# Bomp-countdown.net
KiCad netlist of a schematic drawn in Altium Designer
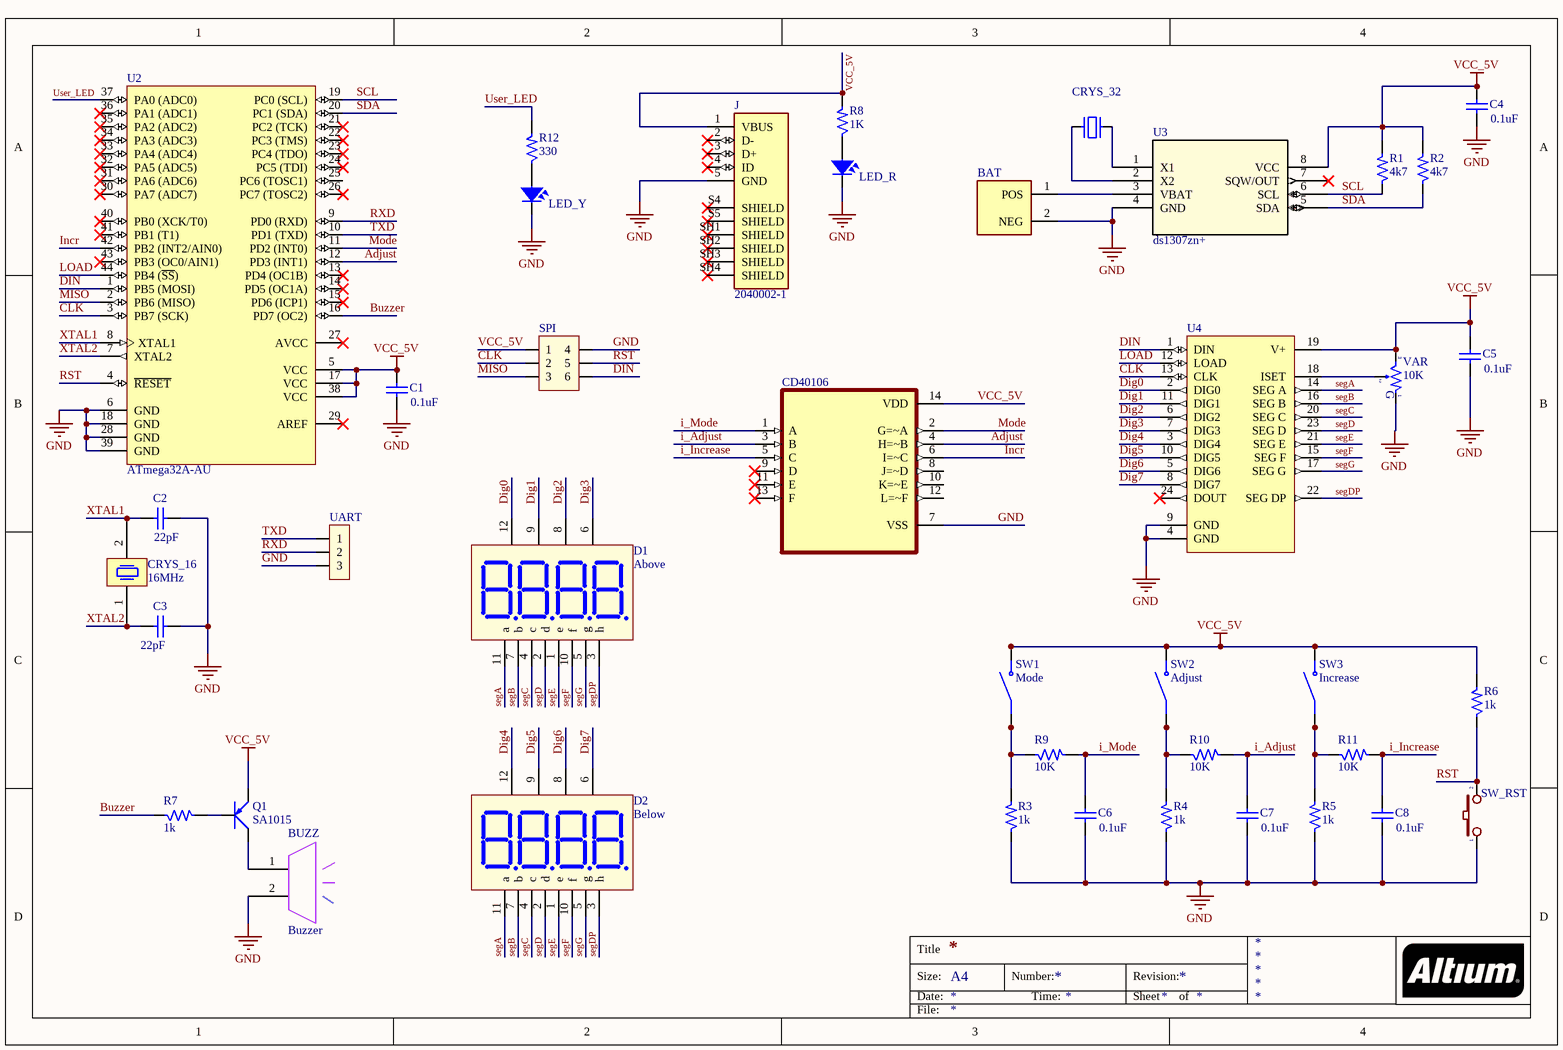
[diagram p0: Bomp-countdown.SchDoc]

(export (version "E")
  (design (tool "Eeschema 10.0.6"))
  (components
    (comp (ref "BAT")
      (value "796136-1")
      (footprint "SnapEDApcb:TE_796136-1")
      (fields (field (name "MF") "TE Connectivity"))
      (libsource (lib "SnapEDAsch") (part "796136-1"))
    )
    (comp (ref "BUZZ")
      (value "Buzzer")
      (footprint "SPEAKER")
      (libsource (lib "My library altium") (part "Buzzer"))
    )
    (comp (ref "C1")
      (value "0.1uF")
      (footprint "C0805")
      (description "Capacitor")
      (fields (field (name "PUBLISHER") "Altium Limited"))
      (libsource (lib "My Library") (part "CapSMD"))
    )
    (comp (ref "C2")
      (value "22pF")
      (footprint "C0805")
      (description "Capacitor")
      (fields (field (name "PUBLISHER") "Altium Limited"))
      (libsource (lib "My Library") (part "CapSMD"))
    )
    (comp (ref "C3")
      (value "22pF")
      (footprint "C0805")
      (description "Capacitor")
      (fields (field (name "PUBLISHER") "Altium Limited"))
      (libsource (lib "My Library") (part "CapSMD"))
    )
    (comp (ref "C4")
      (value "0.1uF")
      (footprint "C0805")
      (description "Capacitor")
      (fields (field (name "PUBLISHER") "Altium Limited"))
      (libsource (lib "My Library") (part "CapSMD"))
    )
    (comp (ref "C5")
      (value "0.1uF")
      (footprint "C0805")
      (description "Capacitor")
      (fields (field (name "PUBLISHER") "Altium Limited"))
      (libsource (lib "My Library") (part "CapSMD"))
    )
    (comp (ref "C6")
      (value "0.1uF")
      (footprint "C0805")
      (description "Capacitor")
      (fields (field (name "PUBLISHER") "Altium Limited"))
      (libsource (lib "My Library") (part "CapSMD"))
    )
    (comp (ref "C7")
      (value "0.1uF")
      (footprint "C0805")
      (description "Capacitor")
      (fields (field (name "PUBLISHER") "Altium Limited"))
      (libsource (lib "My Library") (part "CapSMD"))
    )
    (comp (ref "C8")
      (value "0.1uF")
      (footprint "C0805")
      (description "Capacitor")
      (fields (field (name "PUBLISHER") "Altium Limited"))
      (libsource (lib "My Library") (part "CapSMD"))
    )
    (comp (ref "CD40106")
      (value "CD40106BM")
      (footprint "SOIC127P600X175-14N")
      (description "CMOS Hex Schmitt Triggers 14-SOIC -55 to 125")
      (fields (field (name "MF") "Texas Instruments"))
      (libsource (lib "CD40106BM") (part "CD40106BM"))
    )
    (comp (ref "CRYS_16")
      (value "16MHz")
      (footprint "ABLS2-8.000MHZ-D4Y-T")
      (description "Crystal, 8 MHz, SMD, 11.4mm x 4.7mm, 30 ppm, 18 pF, 30 ppm, ABLS2 Series")
      (fields
        (field (name "MANUFACTURER") "ABRACON")
        (field (name "MANUFACTURER PART NO") "ABLS2-8.000MHZ-D4Y-T")
      )
      (libsource (lib "AltiumOpenLibs") (part "ABLS2-8.000MHZ-D4Y-T"))
    )
    (comp (ref "CRYS_32")
      (value "32.768Khz")
      (footprint "XT32k")
      (description "Crystal, 32.768 KHz, -40 to 85 degC, 3.2 x 1.5 x 0.9 mm SMD")
      (libsource (lib "LIBRARY") (part "XT2"))
    )
    (comp (ref "D1")
      (value "Above")
      (footprint "7SEGQ")
      (description "Four 7 Seg Dipslay")
      (libsource (lib "syhaunguyen") (part "LED7Q"))
    )
    (comp (ref "D2")
      (value "Below")
      (footprint "7SEGQ")
      (description "Four 7 Seg Dipslay")
      (libsource (lib "syhaunguyen") (part "LED7Q"))
    )
    (comp (ref "J")
      (value "2040002-1")
      (footprint "TE_2040002-1")
      (description "Conn Micro USB 2.0 Type B RCP 5 POS 0.65mm Solder RA SMD 5 Terminal 1 Port T/R")
      (fields (field (name "MF") "TE Connectivity"))
      (libsource (lib "u_USB") (part "2040002-1"))
    )
    (comp (ref "LED_R")
      (value "LED SMD")
      (footprint "SM-LED-0805-Red")
      (libsource (lib "syhaunguyen") (part "LED-SMD-0805"))
    )
    (comp (ref "LED_Y")
      (value "LED SMD")
      (footprint "SM-LED-0805-Red")
      (libsource (lib "syhaunguyen") (part "LED-SMD-0805"))
    )
    (comp (ref "Q1")
      (value "SA1015")
      (footprint "SOT23-321")
      (description "PNP 600mW, ECB")
      (libsource (lib "LIBRARY") (part "2SA1015"))
    )
    (comp (ref "R1")
      (value "4k7")
      (footprint "SM-RES-1206")
      (description "Resistor 1/4W")
      (libsource (lib "syhaunguyen") (part "R"))
    )
    (comp (ref "R2")
      (value "4k7")
      (footprint "SM-RES-1206")
      (description "Resistor 1/4W")
      (libsource (lib "syhaunguyen") (part "R"))
    )
    (comp (ref "R3")
      (value "1k")
      (footprint "SM-RES-1206")
      (description "Resistor 1/4W")
      (libsource (lib "syhaunguyen") (part "R"))
    )
    (comp (ref "R4")
      (value "1k")
      (footprint "SM-RES-1206")
      (description "Resistor 1/4W")
      (libsource (lib "syhaunguyen") (part "R"))
    )
    (comp (ref "R5")
      (value "1k")
      (footprint "SM-RES-1206")
      (description "Resistor 1/4W")
      (libsource (lib "syhaunguyen") (part "R"))
    )
    (comp (ref "R6")
      (value "1k")
      (footprint "SM-RES-1206")
      (description "Resistor 1/4W")
      (libsource (lib "syhaunguyen") (part "R"))
    )
    (comp (ref "R7")
      (value "1k")
      (footprint "SM-RES-1206")
      (description "Resistor for buzzer")
      (libsource (lib "syhaunguyen") (part "R"))
    )
    (comp (ref "R8")
      (value "1K")
      (footprint "SM-RES-1206")
      (description "Resistor for buzzer")
      (libsource (lib "syhaunguyen") (part "R"))
    )
    (comp (ref "R9")
      (value "10K")
      (footprint "SM-RES-1206")
      (description "Resistor 1/4W")
      (libsource (lib "syhaunguyen") (part "R"))
    )
    (comp (ref "R10")
      (value "10K")
      (footprint "SM-RES-1206")
      (description "Resistor 1/4W")
      (libsource (lib "syhaunguyen") (part "R"))
    )
    (comp (ref "R11")
      (value "10K")
      (footprint "SM-RES-1206")
      (description "Resistor 1/4W")
      (libsource (lib "syhaunguyen") (part "R"))
    )
    (comp (ref "R12")
      (value "330")
      (footprint "SM-RES-1206")
      (description "Resistor for buzzer")
      (libsource (lib "syhaunguyen") (part "R"))
    )
    (comp (ref "SPI")
      (value "Connector 3x2")
      (footprint "JP3x2")
      (libsource (lib "syhaunguyen") (part "JP3x2"))
    )
    (comp (ref "SW1")
      (value "Mode")
      (footprint "SnapEDApcb:SW_1571527-1")
      (description "Switch Tactile OFF _ON_ Round Button Gull Wing 0.05A 12VDC 0.98N SMD Bulk")
      (fields (field (name "MP") "1571527-1") (field (name "MF") "TE Connectivity"))
      (libsource (lib "SnapEDAsch") (part "1571527-1"))
    )
    (comp (ref "SW2")
      (value "Adjust")
      (footprint "SnapEDApcb:SW_1571527-1")
      (description "Switch Tactile OFF _ON_ Round Button Gull Wing 0.05A 12VDC 0.98N SMD Bulk")
      (fields (field (name "MP") "1571527-1") (field (name "MF") "TE Connectivity"))
      (libsource (lib "SnapEDAsch") (part "1571527-1"))
    )
    (comp (ref "SW3")
      (value "Increase")
      (footprint "SnapEDApcb:SW_1571527-1")
      (description "Switch Tactile OFF _ON_ Round Button Gull Wing 0.05A 12VDC 0.98N SMD Bulk")
      (fields (field (name "MP") "1571527-1") (field (name "MF") "TE Connectivity"))
      (libsource (lib "SnapEDAsch") (part "1571527-1"))
    )
    (comp (ref "SW_RST")
      (value "RST")
      (footprint "SW1-SMD")
      (description "Switch button 2 pin")
      (libsource (lib "LIBRARY") (part "SW2"))
    )
    (comp (ref "U2")
      (value "ATmega32A-AU")
      (footprint "TQFP44")
      (fields (field (name "PUBLISHER") "Altium Limited"))
      (libsource (lib "LIBRARY") (part "ATmega32A-AU"))
    )
    (comp (ref "U3")
      (value "ds1307zn+")
      (footprint "21-0041B_8_MXM")
      (description "No Description Available")
      (fields (field (name "COPYRIGHT") "Copyright (C) 2021 Ultra Librarian. All rights reserved."))
      (libsource (lib "ds1307zn&plus_") (part "ds1307zn+"))
    )
    (comp (ref "U4")
      (value "MAX7219ENG")
      (footprint "SO24")
      (description "Serially Interfaced, 8-Digit LED Display Driver")
      (fields (field (name "PUBLISHER") "Altium Limited"))
      (libsource (lib "LIBRARY") (part "MAX7219ENG"))
    )
    (comp (ref "UART") (value "Jumper 3") (footprint "JP3") (libsource (lib "syhaunguyen") (part "JP3")))
    (comp (ref "VAR")
      (value "10K")
      (footprint "Library:VR-S1")
      (description "Var Resistor")
      (libsource (lib "Library") (part "VR-S"))
    )
  )
  (nets
    (net (code "1") (name "/Adjust") (class "Default")
      (node (ref "CD40106") (pin "4") (pinfunction "H=~B_4") (pintype "output"))
      (node (ref "U2") (pin "12") (pinfunction "PD3_(INT1)_12") (pintype "bidirectional"))
    )
    (net (code "2") (name "/Buzzer") (class "Default")
      (node (ref "R7") (pin "1") (pinfunction "1_1") (pintype "passive"))
      (node (ref "U2") (pin "16") (pinfunction "PD7_(OC2)_16") (pintype "bidirectional"))
    )
    (net (code "3") (name "/CLK") (class "Default")
      (node (ref "SPI") (pin "2") (pinfunction "2_2") (pintype "passive"))
      (node (ref "U2") (pin "3") (pinfunction "PB7_(SCK)_3") (pintype "bidirectional"))
      (node (ref "U4") (pin "13") (pinfunction "CLK_13") (pintype "bidirectional"))
    )
    (net (code "4") (name "/DIN") (class "Default")
      (node (ref "SPI") (pin "6") (pinfunction "6_6") (pintype "passive"))
      (node (ref "U2") (pin "1") (pinfunction "PB5_(MOSI)_1") (pintype "bidirectional"))
      (node (ref "U4") (pin "1") (pinfunction "DIN_1") (pintype "bidirectional"))
    )
    (net (code "5") (name "/Dig0") (class "Default")
      (node (ref "D1") (pin "12") (pinfunction "V1_12") (pintype "passive"))
      (node (ref "U4") (pin "2") (pinfunction "DIG0_2") (pintype "output"))
    )
    (net (code "6") (name "/Dig1") (class "Default")
      (node (ref "D1") (pin "9") (pinfunction "V2_9") (pintype "passive"))
      (node (ref "U4") (pin "11") (pinfunction "DIG1_11") (pintype "output"))
    )
    (net (code "7") (name "/Dig2") (class "Default")
      (node (ref "D1") (pin "8") (pinfunction "V3_8") (pintype "passive"))
      (node (ref "U4") (pin "6") (pinfunction "DIG2_6") (pintype "output"))
    )
    (net (code "8") (name "/Dig3") (class "Default")
      (node (ref "D1") (pin "6") (pinfunction "V4_6") (pintype "passive"))
      (node (ref "U4") (pin "7") (pinfunction "DIG3_7") (pintype "output"))
    )
    (net (code "9") (name "/Dig4") (class "Default")
      (node (ref "D2") (pin "12") (pinfunction "V1_12") (pintype "passive"))
      (node (ref "U4") (pin "3") (pinfunction "DIG4_3") (pintype "output"))
    )
    (net (code "10") (name "/Dig5") (class "Default")
      (node (ref "D2") (pin "9") (pinfunction "V2_9") (pintype "passive"))
      (node (ref "U4") (pin "10") (pinfunction "DIG5_10") (pintype "output"))
    )
    (net (code "11") (name "/Dig6") (class "Default")
      (node (ref "D2") (pin "8") (pinfunction "V3_8") (pintype "passive"))
      (node (ref "U4") (pin "5") (pinfunction "DIG6_5") (pintype "output"))
    )
    (net (code "12") (name "/Dig7") (class "Default")
      (node (ref "D2") (pin "6") (pinfunction "V4_6") (pintype "passive"))
      (node (ref "U4") (pin "8") (pinfunction "DIG7_8") (pintype "output"))
    )
    (net (code "13") (name "/Incr") (class "Default")
      (node (ref "CD40106") (pin "6") (pinfunction "I=~C_6") (pintype "output"))
      (node (ref "U2") (pin "42") (pinfunction "PB2_(INT2/AIN0)_42") (pintype "bidirectional"))
    )
    (net (code "14") (name "/LOAD") (class "Default")
      (node (ref "U2") (pin "44") (pinfunction "PB4_(~{SS})_44") (pintype "bidirectional"))
      (node (ref "U4") (pin "12") (pinfunction "LOAD_12") (pintype "bidirectional"))
    )
    (net (code "15") (name "/MISO") (class "Default")
      (node (ref "SPI") (pin "3") (pinfunction "3_3") (pintype "passive"))
      (node (ref "U2") (pin "2") (pinfunction "PB6_(MISO)_2") (pintype "bidirectional"))
    )
    (net (code "16") (name "/Mode") (class "Default")
      (node (ref "CD40106") (pin "2") (pinfunction "G=~A_2") (pintype "output"))
      (node (ref "U2") (pin "11") (pinfunction "PD2_(INT0)_11") (pintype "bidirectional"))
    )
    (net (code "17") (name "/RST") (class "Default")
      (node (ref "R6") (pin "1") (pinfunction "1_1") (pintype "passive"))
      (node (ref "SPI") (pin "5") (pinfunction "5_5") (pintype "passive"))
      (node (ref "SW_RST") (pin "2") (pinfunction "2_2") (pintype "passive"))
      (node (ref "U2") (pin "4") (pinfunction "~{RESET}_4") (pintype "bidirectional"))
    )
    (net (code "18") (name "/RXD") (class "Default")
      (node (ref "U2") (pin "9") (pinfunction "PD0_(RXD)_9") (pintype "bidirectional"))
      (node (ref "UART") (pin "2") (pinfunction "2_2") (pintype "passive"))
    )
    (net (code "19") (name "/SCL") (class "Default")
      (node (ref "R1") (pin "1") (pinfunction "1_1") (pintype "passive"))
      (node (ref "U2") (pin "19") (pinfunction "PC0_(SCL)_19") (pintype "bidirectional"))
      (node (ref "U3") (pin "6") (pinfunction "SCL_6") (pintype "bidirectional"))
    )
    (net (code "20") (name "/SDA") (class "Default")
      (node (ref "R2") (pin "1") (pinfunction "1_1") (pintype "passive"))
      (node (ref "U2") (pin "20") (pinfunction "PC1_(SDA)_20") (pintype "bidirectional"))
      (node (ref "U3") (pin "5") (pinfunction "SDA_5") (pintype "bidirectional"))
    )
    (net (code "21") (name "/TXD") (class "Default")
      (node (ref "U2") (pin "10") (pinfunction "PD1_(TXD)_10") (pintype "bidirectional"))
      (node (ref "UART") (pin "1") (pinfunction "1_1") (pintype "passive"))
    )
    (net (code "22") (name "/User_LED") (class "Default")
      (node (ref "R12") (pin "2") (pinfunction "2_2") (pintype "passive"))
      (node (ref "U2") (pin "37") (pinfunction "PA0_(ADC0)_37") (pintype "bidirectional"))
    )
    (net (code "23") (name "/XTAL1") (class "Default")
      (node (ref "C2") (pin "1") (pinfunction "1_1") (pintype "passive"))
      (node (ref "CRYS_16") (pin "2") (pinfunction "2_2") (pintype "passive"))
      (node (ref "U2") (pin "8") (pinfunction "XTAL1_8") (pintype "input"))
    )
    (net (code "24") (name "/XTAL2") (class "Default")
      (node (ref "C3") (pin "1") (pinfunction "1_1") (pintype "passive"))
      (node (ref "CRYS_16") (pin "1") (pinfunction "1_1") (pintype "passive"))
      (node (ref "U2") (pin "7") (pinfunction "XTAL2_7") (pintype "output"))
    )
    (net (code "25") (name "/i_Adjust") (class "Default")
      (node (ref "C7") (pin "2") (pinfunction "2_2") (pintype "passive"))
      (node (ref "CD40106") (pin "3") (pinfunction "B_3") (pintype "input"))
      (node (ref "R10") (pin "2") (pinfunction "2_2") (pintype "passive"))
    )
    (net (code "26") (name "/i_Increase") (class "Default")
      (node (ref "C8") (pin "2") (pinfunction "2_2") (pintype "passive"))
      (node (ref "CD40106") (pin "5") (pinfunction "C_5") (pintype "input"))
      (node (ref "R11") (pin "2") (pinfunction "2_2") (pintype "passive"))
    )
    (net (code "27") (name "/i_Mode") (class "Default")
      (node (ref "C6") (pin "2") (pinfunction "2_2") (pintype "passive"))
      (node (ref "CD40106") (pin "1") (pinfunction "A_1") (pintype "input"))
      (node (ref "R9") (pin "2") (pinfunction "2_2") (pintype "passive"))
    )
    (net (code "28") (name "/segA") (class "Default")
      (node (ref "D1") (pin "11") (pinfunction "a_11") (pintype "passive"))
      (node (ref "D2") (pin "11") (pinfunction "a_11") (pintype "passive"))
      (node (ref "U4") (pin "14") (pinfunction "SEG_A_14") (pintype "output"))
    )
    (net (code "29") (name "/segB") (class "Default")
      (node (ref "D1") (pin "7") (pinfunction "b_7") (pintype "passive"))
      (node (ref "D2") (pin "7") (pinfunction "b_7") (pintype "passive"))
      (node (ref "U4") (pin "16") (pinfunction "SEG_B_16") (pintype "output"))
    )
    (net (code "30") (name "/segC") (class "Default")
      (node (ref "D1") (pin "4") (pinfunction "c_4") (pintype "passive"))
      (node (ref "D2") (pin "4") (pinfunction "c_4") (pintype "passive"))
      (node (ref "U4") (pin "20") (pinfunction "SEG_C_20") (pintype "output"))
    )
    (net (code "31") (name "/segD") (class "Default")
      (node (ref "D1") (pin "2") (pinfunction "d_2") (pintype "passive"))
      (node (ref "D2") (pin "2") (pinfunction "d_2") (pintype "passive"))
      (node (ref "U4") (pin "23") (pinfunction "SEG_D_23") (pintype "output"))
    )
    (net (code "32") (name "/segDP") (class "Default")
      (node (ref "D1") (pin "3") (pinfunction "h_3") (pintype "passive"))
      (node (ref "D2") (pin "3") (pinfunction "h_3") (pintype "passive"))
      (node (ref "U4") (pin "22") (pinfunction "SEG_DP_22") (pintype "output"))
    )
    (net (code "33") (name "/segE") (class "Default")
      (node (ref "D1") (pin "1") (pinfunction "e_1") (pintype "passive"))
      (node (ref "D2") (pin "1") (pinfunction "e_1") (pintype "passive"))
      (node (ref "U4") (pin "21") (pinfunction "SEG_E_21") (pintype "output"))
    )
    (net (code "34") (name "/segF") (class "Default")
      (node (ref "D1") (pin "10") (pinfunction "f_10") (pintype "passive"))
      (node (ref "D2") (pin "10") (pinfunction "f_10") (pintype "passive"))
      (node (ref "U4") (pin "15") (pinfunction "SEG_F_15") (pintype "output"))
    )
    (net (code "35") (name "/segG") (class "Default")
      (node (ref "D1") (pin "5") (pinfunction "g_5") (pintype "passive"))
      (node (ref "D2") (pin "5") (pinfunction "g_5") (pintype "passive"))
      (node (ref "U4") (pin "17") (pinfunction "SEG_G_17") (pintype "output"))
    )
    (net (code "36") (name "GND") (class "Default")
      (node (ref "BAT") (pin "2") (pinfunction "NEG_2") (pintype "passive"))
      (node (ref "BUZZ") (pin "2") (pinfunction "2_2") (pintype "passive"))
      (node (ref "C1") (pin "1") (pinfunction "1_1") (pintype "passive"))
      (node (ref "C2") (pin "2") (pinfunction "2_2") (pintype "passive"))
      (node (ref "C3") (pin "2") (pinfunction "2_2") (pintype "passive"))
      (node (ref "C4") (pin "1") (pinfunction "1_1") (pintype "passive"))
      (node (ref "C5") (pin "1") (pinfunction "1_1") (pintype "passive"))
      (node (ref "C6") (pin "1") (pinfunction "1_1") (pintype "passive"))
      (node (ref "C7") (pin "1") (pinfunction "1_1") (pintype "passive"))
      (node (ref "C8") (pin "1") (pinfunction "1_1") (pintype "passive"))
      (node (ref "CD40106") (pin "7") (pinfunction "VSS_7") (pintype "power_in"))
      (node (ref "J") (pin "5") (pinfunction "GND_5") (pintype "power_in"))
      (node (ref "LED_R") (pin "2") (pinfunction "2_2") (pintype "passive"))
      (node (ref "LED_Y") (pin "2") (pinfunction "2_2") (pintype "passive"))
      (node (ref "R3") (pin "1") (pinfunction "1_1") (pintype "passive"))
      (node (ref "R4") (pin "1") (pinfunction "1_1") (pintype "passive"))
      (node (ref "R5") (pin "1") (pinfunction "1_1") (pintype "passive"))
      (node (ref "SPI") (pin "4") (pinfunction "4_4") (pintype "passive"))
      (node (ref "SW_RST") (pin "1") (pinfunction "1_1") (pintype "passive"))
      (node (ref "U2") (pin "18") (pinfunction "GND_18") (pintype "passive"))
      (node (ref "U2") (pin "28") (pinfunction "GND_28") (pintype "passive"))
      (node (ref "U2") (pin "39") (pinfunction "GND_39") (pintype "passive"))
      (node (ref "U2") (pin "6") (pinfunction "GND_6") (pintype "passive"))
      (node (ref "U3") (pin "4") (pinfunction "GND_4") (pintype "power_in"))
      (node (ref "U4") (pin "4") (pinfunction "GND_4") (pintype "power_in"))
      (node (ref "U4") (pin "9") (pinfunction "GND_9") (pintype "power_in"))
      (node (ref "UART") (pin "3") (pinfunction "3_3") (pintype "passive"))
      (node (ref "VAR") (pin "1") (pinfunction "1_1") (pintype "passive"))
    )
    (net (code "37") (name "Net-(BAT-POS)") (class "Default")
      (node (ref "BAT") (pin "1") (pinfunction "POS_1") (pintype "passive"))
      (node (ref "U3") (pin "3") (pinfunction "VBAT_3") (pintype "power_in"))
    )
    (net (code "38") (name "Net-(LED_R-Pad1)") (class "Default")
      (node (ref "LED_R") (pin "1") (pinfunction "1_1") (pintype "passive"))
      (node (ref "R8") (pin "1") (pinfunction "1_1") (pintype "passive"))
    )
    (net (code "39") (name "Net-(LED_Y-Pad1)") (class "Default")
      (node (ref "LED_Y") (pin "1") (pinfunction "1_1") (pintype "passive"))
      (node (ref "R12") (pin "1") (pinfunction "1_1") (pintype "passive"))
    )
    (net (code "40") (name "Net-(Q1-B)") (class "Default")
      (node (ref "Q1") (pin "3") (pinfunction "B_3") (pintype "passive"))
      (node (ref "R7") (pin "2") (pinfunction "2_2") (pintype "passive"))
    )
    (net (code "41") (name "Net-(Q1-C)") (class "Default")
      (node (ref "BUZZ") (pin "1") (pinfunction "1_1") (pintype "passive"))
      (node (ref "Q1") (pin "2") (pinfunction "C_2") (pintype "passive"))
    )
    (net (code "42") (name "Net-(R3-Pad2)") (class "Default")
      (node (ref "R3") (pin "2") (pinfunction "2_2") (pintype "passive"))
      (node (ref "R9") (pin "1") (pinfunction "1_1") (pintype "passive"))
      (node (ref "SW1") (pin "1") (pinfunction "COM_1") (pintype "passive"))
      (node (ref "SW1") (pin "2") (pinfunction "COM_2") (pintype "passive"))
    )
    (net (code "43") (name "Net-(R10-Pad1)") (class "Default")
      (node (ref "R10") (pin "1") (pinfunction "1_1") (pintype "passive"))
      (node (ref "R4") (pin "2") (pinfunction "2_2") (pintype "passive"))
      (node (ref "SW2") (pin "1") (pinfunction "COM_1") (pintype "passive"))
      (node (ref "SW2") (pin "2") (pinfunction "COM_2") (pintype "passive"))
    )
    (net (code "44") (name "Net-(R11-Pad1)") (class "Default")
      (node (ref "R11") (pin "1") (pinfunction "1_1") (pintype "passive"))
      (node (ref "R5") (pin "2") (pinfunction "2_2") (pintype "passive"))
      (node (ref "SW3") (pin "1") (pinfunction "COM_1") (pintype "passive"))
      (node (ref "SW3") (pin "2") (pinfunction "COM_2") (pintype "passive"))
    )
    (net (code "45") (name "Net-(U3-X1)") (class "Default")
      (node (ref "CRYS_32") (pin "2") (pinfunction "2_2") (pintype "passive"))
      (node (ref "U3") (pin "1") (pinfunction "X1_1") (pintype "passive"))
    )
    (net (code "46") (name "Net-(U3-X2)") (class "Default")
      (node (ref "CRYS_32") (pin "1") (pinfunction "1_1") (pintype "passive"))
      (node (ref "U3") (pin "2") (pinfunction "X2_2") (pintype "passive"))
    )
    (net (code "47") (name "Net-(U4-ISET)") (class "Default")
      (node (ref "U4") (pin "18") (pinfunction "ISET_18") (pintype "passive"))
      (node (ref "VAR") (pin "2") (pinfunction "2_2") (pintype "passive"))
    )
    (net (code "48") (name "VCC_5V") (class "Default")
      (node (ref "C1") (pin "2") (pinfunction "2_2") (pintype "passive"))
      (node (ref "C4") (pin "2") (pinfunction "2_2") (pintype "passive"))
      (node (ref "C5") (pin "2") (pinfunction "2_2") (pintype "passive"))
      (node (ref "CD40106") (pin "14") (pinfunction "VDD_14") (pintype "power_in"))
      (node (ref "J") (pin "1") (pinfunction "VBUS_1") (pintype "power_in"))
      (node (ref "Q1") (pin "1") (pinfunction "E_1") (pintype "passive"))
      (node (ref "R1") (pin "2") (pinfunction "2_2") (pintype "passive"))
      (node (ref "R2") (pin "2") (pinfunction "2_2") (pintype "passive"))
      (node (ref "R6") (pin "2") (pinfunction "2_2") (pintype "passive"))
      (node (ref "R8") (pin "2") (pinfunction "2_2") (pintype "passive"))
      (node (ref "SPI") (pin "1") (pinfunction "1_1") (pintype "passive"))
      (node (ref "SW1") (pin "3") (pinfunction "NO_3") (pintype "passive"))
      (node (ref "SW1") (pin "4") (pinfunction "NO_4") (pintype "passive"))
      (node (ref "SW2") (pin "3") (pinfunction "NO_3") (pintype "passive"))
      (node (ref "SW2") (pin "4") (pinfunction "NO_4") (pintype "passive"))
      (node (ref "SW3") (pin "3") (pinfunction "NO_3") (pintype "passive"))
      (node (ref "SW3") (pin "4") (pinfunction "NO_4") (pintype "passive"))
      (node (ref "U2") (pin "17") (pinfunction "VCC_17") (pintype "passive"))
      (node (ref "U2") (pin "38") (pinfunction "VCC_38") (pintype "passive"))
      (node (ref "U2") (pin "5") (pinfunction "VCC_5") (pintype "passive"))
      (node (ref "U3") (pin "8") (pinfunction "VCC_8") (pintype "power_in"))
      (node (ref "U4") (pin "19") (pinfunction "V+_19") (pintype "power_in"))
      (node (ref "VAR") (pin "3") (pinfunction "3_3") (pintype "passive"))
    )
    (net (code "49") (name "unconnected-(CD40106-D-Pad9)") (class "Default")
      (node (ref "CD40106") (pin "9") (pinfunction "D_9") (pintype "input+no_connect"))
    )
    (net (code "50") (name "unconnected-(CD40106-E-Pad11)") (class "Default")
      (node (ref "CD40106") (pin "11") (pinfunction "E_11") (pintype "input+no_connect"))
    )
    (net (code "51") (name "unconnected-(CD40106-F-Pad13)") (class "Default")
      (node (ref "CD40106") (pin "13") (pinfunction "F_13") (pintype "input+no_connect"))
    )
    (net (code "52") (name "unconnected-(CD40106-J=~D-Pad8)") (class "Default")
      (node (ref "CD40106") (pin "8") (pinfunction "J=~D_8") (pintype "output"))
    )
    (net (code "53") (name "unconnected-(CD40106-K=~E-Pad10)") (class "Default")
      (node (ref "CD40106") (pin "10") (pinfunction "K=~E_10") (pintype "output"))
    )
    (net (code "54") (name "unconnected-(CD40106-L=~F-Pad12)") (class "Default")
      (node (ref "CD40106") (pin "12") (pinfunction "L=~F_12") (pintype "output"))
    )
    (net (code "55") (name "unconnected-(J-D+-Pad3)") (class "Default")
      (node (ref "J") (pin "3") (pinfunction "D+_3") (pintype "bidirectional+no_connect"))
    )
    (net (code "56") (name "unconnected-(J-D--Pad2)") (class "Default")
      (node (ref "J") (pin "2") (pinfunction "D-_2") (pintype "bidirectional+no_connect"))
    )
    (net (code "57") (name "unconnected-(J-ID-Pad4)") (class "Default")
      (node (ref "J") (pin "4") (pinfunction "ID_4") (pintype "bidirectional+no_connect"))
    )
    (net (code "58") (name "unconnected-(J-SHIELD-PadS4)") (class "Default")
      (node (ref "J") (pin "S4") (pinfunction "SHIELD_S4") (pintype "power_in+no_connect"))
    )
    (net (code "59") (name "unconnected-(J-SHIELD-PadS5)") (class "Default")
      (node (ref "J") (pin "S5") (pinfunction "SHIELD_S5") (pintype "power_in+no_connect"))
    )
    (net (code "60") (name "unconnected-(J-SHIELD-PadSH1)") (class "Default")
      (node (ref "J") (pin "SH1") (pinfunction "SHIELD_SH1") (pintype "power_in+no_connect"))
    )
    (net (code "61") (name "unconnected-(J-SHIELD-PadSH2)") (class "Default")
      (node (ref "J") (pin "SH2") (pinfunction "SHIELD_SH2") (pintype "power_in+no_connect"))
    )
    (net (code "62") (name "unconnected-(J-SHIELD-PadSH3)") (class "Default")
      (node (ref "J") (pin "SH3") (pinfunction "SHIELD_SH3") (pintype "power_in+no_connect"))
    )
    (net (code "63") (name "unconnected-(J-SHIELD-PadSH4)") (class "Default")
      (node (ref "J") (pin "SH4") (pinfunction "SHIELD_SH4") (pintype "power_in+no_connect"))
    )
    (net (code "64") (name "unconnected-(U2-AREF-Pad29)") (class "Default")
      (node (ref "U2") (pin "29") (pinfunction "AREF_29") (pintype "power_in+no_connect"))
    )
    (net (code "65") (name "unconnected-(U2-AVCC-Pad27)") (class "Default")
      (node (ref "U2") (pin "27") (pinfunction "AVCC_27") (pintype "power_in+no_connect"))
    )
    (net (code "66") (name "unconnected-(U2-PA1_(ADC1)-Pad36)") (class "Default")
      (node (ref "U2") (pin "36") (pinfunction "PA1_(ADC1)_36") (pintype "bidirectional+no_connect"))
    )
    (net (code "67") (name "unconnected-(U2-PA2_(ADC2)-Pad35)") (class "Default")
      (node (ref "U2") (pin "35") (pinfunction "PA2_(ADC2)_35") (pintype "bidirectional+no_connect"))
    )
    (net (code "68") (name "unconnected-(U2-PA3_(ADC3)-Pad34)") (class "Default")
      (node (ref "U2") (pin "34") (pinfunction "PA3_(ADC3)_34") (pintype "bidirectional+no_connect"))
    )
    (net (code "69") (name "unconnected-(U2-PA4_(ADC4)-Pad33)") (class "Default")
      (node (ref "U2") (pin "33") (pinfunction "PA4_(ADC4)_33") (pintype "bidirectional+no_connect"))
    )
    (net (code "70") (name "unconnected-(U2-PA5_(ADC5)-Pad32)") (class "Default")
      (node (ref "U2") (pin "32") (pinfunction "PA5_(ADC5)_32") (pintype "bidirectional+no_connect"))
    )
    (net (code "71") (name "unconnected-(U2-PA6_(ADC6)-Pad31)") (class "Default")
      (node (ref "U2") (pin "31") (pinfunction "PA6_(ADC6)_31") (pintype "bidirectional+no_connect"))
    )
    (net (code "72") (name "unconnected-(U2-PA7_(ADC7)-Pad30)") (class "Default")
      (node (ref "U2") (pin "30") (pinfunction "PA7_(ADC7)_30") (pintype "bidirectional+no_connect"))
    )
    (net (code "73") (name "unconnected-(U2-PB0_(XCK{slash}T0)-Pad40)") (class "Default")
      (node (ref "U2") (pin "40") (pinfunction "PB0_(XCK/T0)_40") (pintype "bidirectional+no_connect"))
    )
    (net (code "74") (name "unconnected-(U2-PB1_(T1)-Pad41)") (class "Default")
      (node (ref "U2") (pin "41") (pinfunction "PB1_(T1)_41") (pintype "bidirectional+no_connect"))
    )
    (net (code "75") (name "unconnected-(U2-PB3_(OC0{slash}AIN1)-Pad43)") (class "Default")
      (node (ref "U2") (pin "43") (pinfunction "PB3_(OC0/AIN1)_43") (pintype "bidirectional+no_connect"))
    )
    (net (code "76") (name "unconnected-(U2-PC2_(TCK)-Pad21)") (class "Default")
      (node (ref "U2") (pin "21") (pinfunction "PC2_(TCK)_21") (pintype "bidirectional+no_connect"))
    )
    (net (code "77") (name "unconnected-(U2-PC3_(TMS)-Pad22)") (class "Default")
      (node (ref "U2") (pin "22") (pinfunction "PC3_(TMS)_22") (pintype "bidirectional+no_connect"))
    )
    (net (code "78") (name "unconnected-(U2-PC4_(TDO)-Pad23)") (class "Default")
      (node (ref "U2") (pin "23") (pinfunction "PC4_(TDO)_23") (pintype "bidirectional+no_connect"))
    )
    (net (code "79") (name "unconnected-(U2-PC5_(TDI)-Pad24)") (class "Default")
      (node (ref "U2") (pin "24") (pinfunction "PC5_(TDI)_24") (pintype "bidirectional+no_connect"))
    )
    (net (code "80") (name "unconnected-(U2-PC6_(TOSC1)-Pad25)") (class "Default")
      (node (ref "U2") (pin "25") (pinfunction "PC6_(TOSC1)_25") (pintype "bidirectional"))
    )
    (net (code "81") (name "unconnected-(U2-PC7_(TOSC2)-Pad26)") (class "Default")
      (node (ref "U2") (pin "26") (pinfunction "PC7_(TOSC2)_26") (pintype "bidirectional+no_connect"))
    )
    (net (code "82") (name "unconnected-(U2-PD4_(OC1B)-Pad13)") (class "Default")
      (node (ref "U2") (pin "13") (pinfunction "PD4_(OC1B)_13") (pintype "bidirectional+no_connect"))
    )
    (net (code "83") (name "unconnected-(U2-PD5_(OC1A)-Pad14)") (class "Default")
      (node (ref "U2") (pin "14") (pinfunction "PD5_(OC1A)_14") (pintype "bidirectional+no_connect"))
    )
    (net (code "84") (name "unconnected-(U2-PD6_(ICP1)-Pad15)") (class "Default")
      (node (ref "U2") (pin "15") (pinfunction "PD6_(ICP1)_15") (pintype "bidirectional+no_connect"))
    )
    (net (code "85") (name "unconnected-(U3-SQW{slash}OUT-Pad7)") (class "Default")
      (node (ref "U3") (pin "7") (pinfunction "SQW/OUT_7") (pintype "output+no_connect"))
    )
    (net (code "86") (name "unconnected-(U4-DOUT-Pad24)") (class "Default")
      (node (ref "U4") (pin "24") (pinfunction "DOUT_24") (pintype "output+no_connect"))
    )
  )
)
